# SH1-MCU.net
KiCad netlist of a schematic drawn in Altium Designer
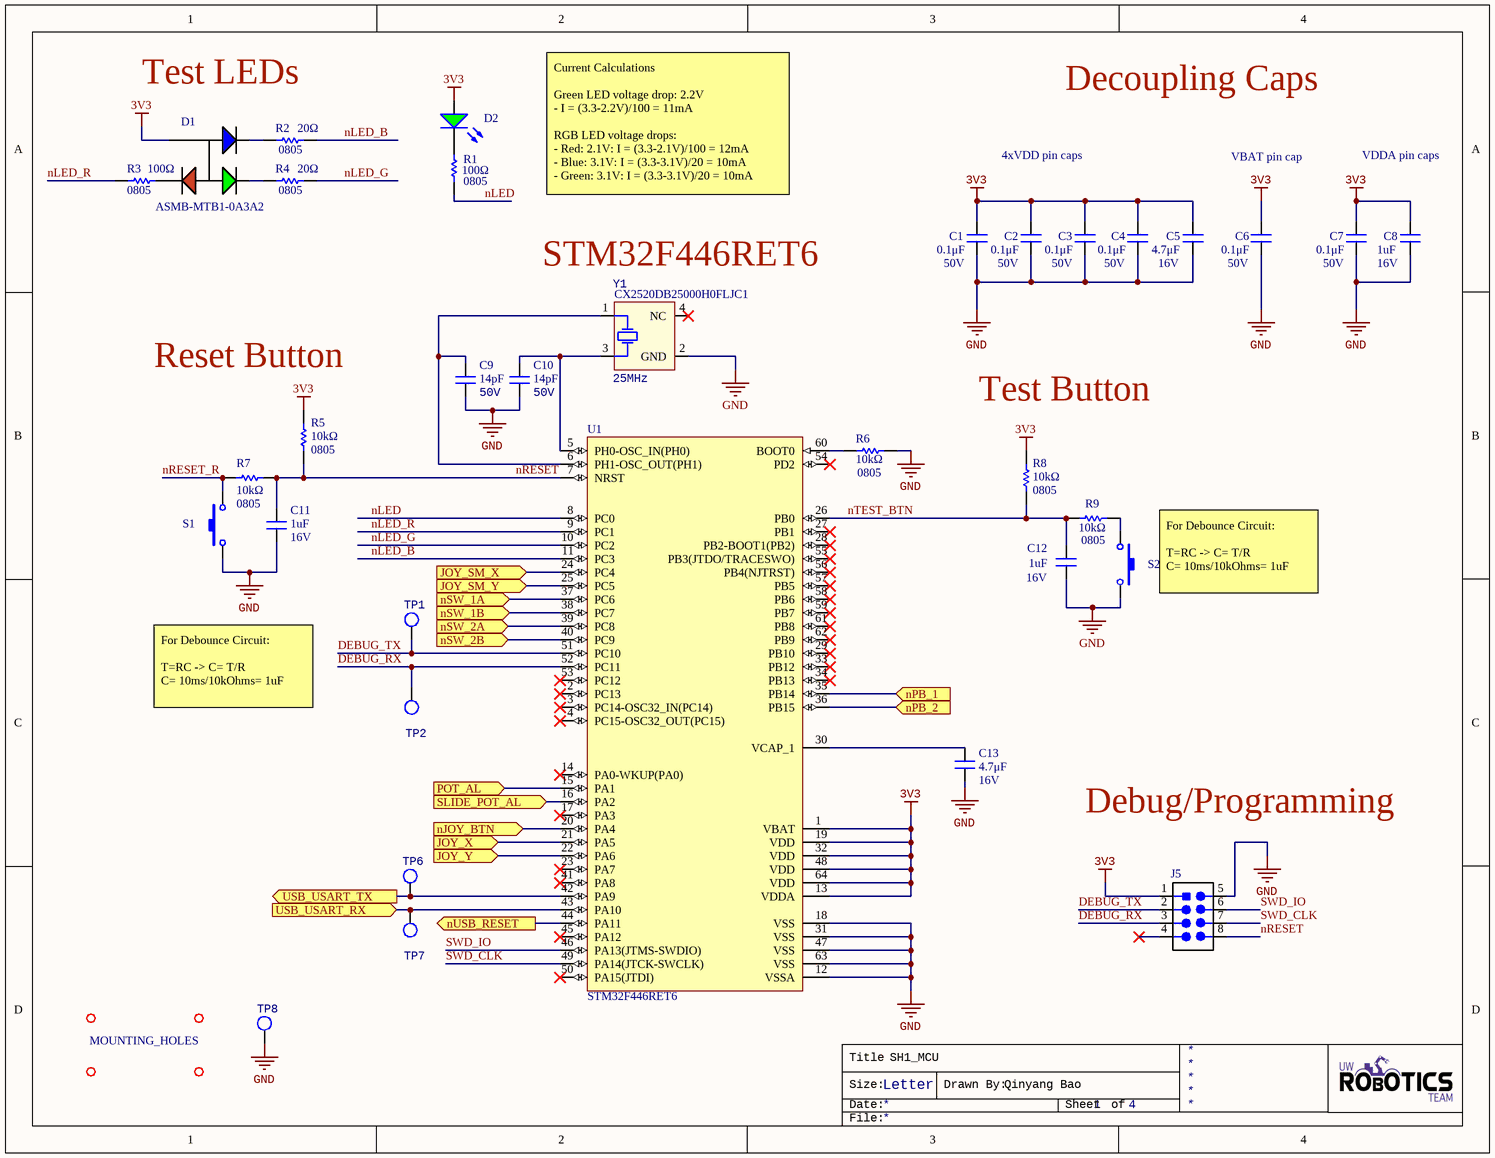
[diagram p0: SH1-MCU.SchDoc]

(export (version "E")
  (design (tool "Eeschema 10.0.6"))
  (components
    (comp (ref "C1")
      (value "0.1μF")
      (footprint "CAPC2012X140N")
      (description "CAP CER 0.1UF 50V X7R 0805")
      (fields (field (name "TOLERANCE") "10%") (field (name "VOLTAGE RATING") "50V"))
      (libsource (lib "UWRT_Schematic_Library_2020") (part "CAP_0.1uF_50V_0805"))
    )
    (comp (ref "C2")
      (value "0.1μF")
      (footprint "CAPC2012X140N")
      (description "CAP CER 0.1UF 50V X7R 0805")
      (fields (field (name "TOLERANCE") "10%") (field (name "VOLTAGE RATING") "50V"))
      (libsource (lib "UWRT_Schematic_Library_2020") (part "CAP_0.1uF_50V_0805"))
    )
    (comp (ref "C3")
      (value "0.1μF")
      (footprint "CAPC2012X140N")
      (description "CAP CER 0.1UF 50V X7R 0805")
      (fields (field (name "TOLERANCE") "10%") (field (name "VOLTAGE RATING") "50V"))
      (libsource (lib "UWRT_Schematic_Library_2020") (part "CAP_0.1uF_50V_0805"))
    )
    (comp (ref "C4")
      (value "0.1μF")
      (footprint "CAPC2012X140N")
      (description "CAP CER 0.1UF 50V X7R 0805")
      (fields (field (name "TOLERANCE") "10%") (field (name "VOLTAGE RATING") "50V"))
      (libsource (lib "UWRT_Schematic_Library_2020") (part "CAP_0.1uF_50V_0805"))
    )
    (comp (ref "C5")
      (value "4.7μF")
      (footprint "CAPC2012X140N")
      (description "CAP CER 4.7UF 16V X5R 0805")
      (fields
        (field (name "TOLERANCE") "10%")
        (field (name "VOLTAGE RATING") "16V")
        (field (name "Comment") "CAP_4.7uF_16V_0805")
      )
      (libsource (lib "UWRT_Schematic_Library_2020") (part "CAP_4.7uF_16V_0805"))
    )
    (comp (ref "C6")
      (value "0.1μF")
      (footprint "CAPC2012X140N")
      (description "CAP CER 0.1UF 50V X7R 0805")
      (fields (field (name "TOLERANCE") "10%") (field (name "VOLTAGE RATING") "50V"))
      (libsource (lib "UWRT_Schematic_Library_2020") (part "CAP_0.1uF_50V_0805"))
    )
    (comp (ref "C7")
      (value "0.1μF")
      (footprint "CAPC2012X140N")
      (description "CAP CER 0.1UF 50V X7R 0805")
      (fields (field (name "TOLERANCE") "10%") (field (name "VOLTAGE RATING") "50V"))
      (libsource (lib "UWRT_Schematic_Library_2020") (part "CAP_0.1uF_50V_0805"))
    )
    (comp (ref "C8")
      (value "1uF")
      (footprint "CAPC2012X140N")
      (description "CAP CER 1UF 16V X7R 0805")
      (fields
        (field (name "TOLERANCE") "10%")
        (field (name "VOLTAGE RATING") "16V")
        (field (name "Comment") "CAP_1uF_16V_0805")
      )
      (libsource (lib "UWRT_Schematic_Library_2020") (part "CAP_1uF_16V_0805"))
    )
    (comp (ref "C9")
      (value "14pF")
      (footprint "CAPC0603(1608)55_N")
      (description "Cap Ceramic 14pF 50V C0G 5% SMD 0603 125C Cardboard T/R")
      (fields
        (field (name "TOLERANCE") "5%")
        (field (name "VOLTAGE RATING (DC)") "50V")
        (field (name "Comment") "CL10C140JB8NNNC")
      )
      (libsource (lib "UWRT_Schematic_Library_2020") (part "CL10C140JB8NNNC"))
    )
    (comp (ref "C10")
      (value "14pF")
      (footprint "CAPC0603(1608)55_N")
      (description "Cap Ceramic 14pF 50V C0G 5% SMD 0603 125C Cardboard T/R")
      (fields
        (field (name "TOLERANCE") "5%")
        (field (name "VOLTAGE RATING (DC)") "50V")
        (field (name "Comment") "CL10C140JB8NNNC")
      )
      (libsource (lib "UWRT_Schematic_Library_2020") (part "CL10C140JB8NNNC"))
    )
    (comp (ref "C11")
      (value "1uF")
      (footprint "CAPC2012X140N")
      (description "CAP CER 1UF 16V X7R 0805")
      (fields
        (field (name "TOLERANCE") "10%")
        (field (name "VOLTAGE RATING") "16V")
        (field (name "Comment") "CAP_1uF_16V_0805")
      )
      (libsource (lib "UWRT_Schematic_Library_2020") (part "CAP_1uF_16V_0805"))
    )
    (comp (ref "C12")
      (value "1uF")
      (footprint "CAPC2012X140N")
      (description "CAP CER 1UF 16V X7R 0805")
      (fields
        (field (name "TOLERANCE") "10%")
        (field (name "VOLTAGE RATING") "16V")
        (field (name "Comment") "CAP_1uF_16V_0805")
      )
      (libsource (lib "UWRT_Schematic_Library_2020") (part "CAP_1uF_16V_0805"))
    )
    (comp (ref "C13")
      (value "4.7μF")
      (footprint "CAPC2012X140N")
      (description "CAP CER 4.7UF 16V X5R 0805")
      (fields
        (field (name "TOLERANCE") "10%")
        (field (name "VOLTAGE RATING") "16V")
        (field (name "Comment") "CAP_4.7uF_16V_0805")
      )
      (libsource (lib "UWRT_Schematic_Library_2020") (part "CAP_4.7uF_16V_0805"))
    )
    (comp (ref "D1")
      (value "LED_RGB")
      (footprint "LED_RGB")
      (description "LED RGB DIFFUSED 4PLCC SMD")
      (fields (field (name "MANUFACTURER PART NUMBER 1") "ASMB-MTB1-0A3A2"))
      (libsource (lib "UWRT_Schematic_Library_2020") (part "LED_RGB"))
    )
    (comp (ref "D2")
      (value "LG R971-KN-1")
      (footprint "LED_0805_LINE")
      (description "LED GREEN DIFFUSED 0805 SMD")
      (libsource (lib "UWRT_Schematic_Library_2020") (part "DIO_LED_G"))
    )
    (comp (ref "J5")
      (value "HEADER 4X2")
      (footprint "HEADER_2X4")
      (description "CONN HEADER VERT 8POS 2.54MM")
      (libsource (lib "UWRT_Schematic_Library_2020") (part "HEADER 4X2"))
    )
    (comp (ref "MH1")
      (value "MOUNTING_HOLES")
      (footprint "MOUNTING_HOLE")
      (description "6cm x 6cm")
      (libsource (lib "UWRT_Schematic_Library_2020") (part "MOUNTING_HOLES"))
    )
    (comp (ref "MH2")
      (value "MOUNTING_HOLES")
      (footprint "MOUNTING_HOLE")
      (description "6cm x 6cm")
      (libsource (lib "UWRT_Schematic_Library_2020") (part "MOUNTING_HOLES"))
    )
    (comp (ref "MH3")
      (value "MOUNTING_HOLES")
      (footprint "MOUNTING_HOLE")
      (description "6cm x 6cm")
      (libsource (lib "UWRT_Schematic_Library_2020") (part "MOUNTING_HOLES"))
    )
    (comp (ref "MH4")
      (value "MOUNTING_HOLES")
      (footprint "MOUNTING_HOLE")
      (description "6cm x 6cm")
      (libsource (lib "UWRT_Schematic_Library_2020") (part "MOUNTING_HOLES"))
    )
    (comp (ref "R1")
      (value "100Ω")
      (footprint "RESC2012X60N")
      (description "RES SMD 100 OHM 1% 1/8W 0805")
      (fields (field (name "CASE CODE (IMPERIAL)") "0805") (field (name "Comment") "RES_100Ω_0805"))
      (libsource (lib "UWRT_Schematic_Library_2020") (part "RES_100Ω_0805"))
    )
    (comp (ref "R2")
      (value "20Ω")
      (footprint "RESC2012X60N")
      (description "RES SMD 20 OHM 1% 1/8W 0805")
      (fields
        (field (name "CASE CODE (IMPERIAL)") "0805")
        (field (name "TOLERANCE") "1%")
        (field (name "Comment") "RES_20Ω_0805")
      )
      (libsource (lib "UWRT_Schematic_Library_2020") (part "RES_20Ω_0805"))
    )
    (comp (ref "R3")
      (value "100Ω")
      (footprint "RESC2012X60N")
      (description "RES SMD 100 OHM 1% 1/8W 0805")
      (fields (field (name "CASE CODE (IMPERIAL)") "0805") (field (name "Comment") "RES_100Ω_0805"))
      (libsource (lib "UWRT_Schematic_Library_2020") (part "RES_100Ω_0805"))
    )
    (comp (ref "R4")
      (value "20Ω")
      (footprint "RESC2012X60N")
      (description "RES SMD 20 OHM 1% 1/8W 0805")
      (fields
        (field (name "CASE CODE (IMPERIAL)") "0805")
        (field (name "TOLERANCE") "1%")
        (field (name "Comment") "RES_20Ω_0805")
      )
      (libsource (lib "UWRT_Schematic_Library_2020") (part "RES_20Ω_0805"))
    )
    (comp (ref "R5")
      (value "10kΩ")
      (footprint "RESC2012X60N")
      (description "RES SMD 10K OHM 1% 1/8W 0805")
      (fields
        (field (name "CASE CODE (IMPERIAL)") "0805")
        (field (name "TOLERANCE") "1%")
        (field (name "Comment") "RES_10kΩ_0805")
      )
      (libsource (lib "UWRT_Schematic_Library_2020") (part "RES_10kΩ_0805"))
    )
    (comp (ref "R6")
      (value "10kΩ")
      (footprint "RESC2012X60N")
      (description "RES SMD 10K OHM 1% 1/8W 0805")
      (fields
        (field (name "CASE CODE (IMPERIAL)") "0805")
        (field (name "TOLERANCE") "1%")
        (field (name "Comment") "RES_10kΩ_0805")
      )
      (libsource (lib "UWRT_Schematic_Library_2020") (part "RES_10kΩ_0805"))
    )
    (comp (ref "R7")
      (value "10kΩ")
      (footprint "RESC2012X60N")
      (description "RES SMD 10K OHM 1% 1/8W 0805")
      (fields
        (field (name "CASE CODE (IMPERIAL)") "0805")
        (field (name "TOLERANCE") "1%")
        (field (name "Comment") "RES_10kΩ_0805")
      )
      (libsource (lib "UWRT_Schematic_Library_2020") (part "RES_10kΩ_0805"))
    )
    (comp (ref "R8")
      (value "10kΩ")
      (footprint "RESC2012X60N")
      (description "RES SMD 10K OHM 1% 1/8W 0805")
      (fields
        (field (name "CASE CODE (IMPERIAL)") "0805")
        (field (name "TOLERANCE") "1%")
        (field (name "Comment") "RES_10kΩ_0805")
      )
      (libsource (lib "UWRT_Schematic_Library_2020") (part "RES_10kΩ_0805"))
    )
    (comp (ref "R9")
      (value "10kΩ")
      (footprint "RESC2012X60N")
      (description "RES SMD 10K OHM 1% 1/8W 0805")
      (fields
        (field (name "CASE CODE (IMPERIAL)") "0805")
        (field (name "TOLERANCE") "1%")
        (field (name "Comment") "RES_10kΩ_0805")
      )
      (libsource (lib "UWRT_Schematic_Library_2020") (part "RES_10kΩ_0805"))
    )
    (comp (ref "S1")
      (value "SW_TACTILE")
      (footprint "B3U-1000P")
      (description "Tactile Switch (Grey)")
      (libsource (lib "UWRT_Schematic_Library_2020") (part "SW_TACTILE"))
    )
    (comp (ref "S2")
      (value "SW_TACTILE")
      (footprint "B3U-1000P")
      (description "Tactile Switch (Grey)")
      (libsource (lib "UWRT_Schematic_Library_2020") (part "SW_TACTILE"))
    )
    (comp (ref "TP1")
      (value "TESTPOINT_LOOP")
      (footprint "TESTPOINT_LOOP")
      (description "Loop testpoint through-hole pad")
      (libsource (lib "UWRT_Schematic_Library_2020") (part "TESTPOINT_LOOP"))
    )
    (comp (ref "TP2")
      (value "TESTPOINT_LOOP")
      (footprint "TESTPOINT_LOOP")
      (description "Loop testpoint through-hole pad")
      (libsource (lib "UWRT_Schematic_Library_2020") (part "TESTPOINT_LOOP"))
    )
    (comp (ref "TP6")
      (value "TESTPOINT_LOOP")
      (footprint "TESTPOINT_LOOP")
      (description "Loop testpoint through-hole pad")
      (libsource (lib "UWRT_Schematic_Library_2020") (part "TESTPOINT_LOOP"))
    )
    (comp (ref "TP7")
      (value "TESTPOINT_LOOP")
      (footprint "TESTPOINT_LOOP")
      (description "Loop testpoint through-hole pad")
      (libsource (lib "UWRT_Schematic_Library_2020") (part "TESTPOINT_LOOP"))
    )
    (comp (ref "TP8")
      (value "TESTPOINT_LOOP")
      (footprint "TESTPOINT_LOOP")
      (description "Loop testpoint through-hole pad")
      (libsource (lib "UWRT_Schematic_Library_2020") (part "TESTPOINT_LOOP"))
    )
    (comp (ref "U1")
      (value "STM32F446RET6")
      (footprint "STM-LQFP64_L")
      (libsource (lib "UWRT_Schematic_Library_2020") (part "MCU_STM32F446RET6"))
    )
    (comp (ref "Y1")
      (value "CRYSTAL_25MHZ")
      (footprint "SOIC254P1016X440-4N")
      (description "CRYSTAL 25.0000MHZ 12PF SMD")
      (fields
        (field (name "MANUFACTURER PART NUMBER 1") "CX2520DB25000H0FLJC1")
        (field (name "FREQUENCY") "25MHz")
      )
      (libsource (lib "UWRT_Schematic_Library_2020") (part "CRYSTAL_25MHZ"))
    )
  )
  (nets
    (net (code "1") (name "/DEBUG_RX") (class "Default")
      (node (ref "J5") (pin "3") (pinfunction "3_3") (pintype "passive"))
      (node (ref "TP2") (pin "1") (pintype "passive"))
      (node (ref "U1") (pin "52") (pinfunction "PC11_52") (pintype "bidirectional"))
    )
    (net (code "2") (name "/DEBUG_TX") (class "Default")
      (node (ref "J5") (pin "2") (pinfunction "2_2") (pintype "passive"))
      (node (ref "TP1") (pin "1") (pintype "passive"))
      (node (ref "U1") (pin "51") (pinfunction "PC10_51") (pintype "bidirectional"))
    )
    (net (code "3") (name "/JOY_SM_X") (class "Default")
      (node (ref "U1") (pin "24") (pinfunction "PC4_24") (pintype "bidirectional"))
    )
    (net (code "4") (name "/JOY_SM_Y") (class "Default")
      (node (ref "U1") (pin "25") (pinfunction "PC5_25") (pintype "bidirectional"))
    )
    (net (code "5") (name "/JOY_X") (class "Default")
      (node (ref "U1") (pin "21") (pinfunction "PA5_21") (pintype "bidirectional"))
    )
    (net (code "6") (name "/JOY_Y") (class "Default")
      (node (ref "U1") (pin "22") (pinfunction "PA6_22") (pintype "bidirectional"))
    )
    (net (code "7") (name "/POT_AL") (class "Default")
      (node (ref "U1") (pin "15") (pinfunction "PA1_15") (pintype "bidirectional"))
    )
    (net (code "8") (name "/SLIDE_POT_AL") (class "Default")
      (node (ref "U1") (pin "16") (pinfunction "PA2_16") (pintype "bidirectional"))
    )
    (net (code "9") (name "/SWD_CLK") (class "Default")
      (node (ref "J5") (pin "7") (pinfunction "3_7") (pintype "passive"))
      (node (ref "U1") (pin "49") (pinfunction "PA14(JTCK-SWCLK)_49") (pintype "bidirectional"))
    )
    (net (code "10") (name "/SWD_IO") (class "Default")
      (node (ref "J5") (pin "6") (pinfunction "2_6") (pintype "passive"))
      (node (ref "U1") (pin "46") (pinfunction "PA13(JTMS-SWDIO)_46") (pintype "bidirectional"))
    )
    (net (code "11") (name "/USB_USART_RX") (class "Default")
      (node (ref "TP7") (pin "1") (pintype "passive"))
      (node (ref "U1") (pin "43") (pinfunction "PA10_43") (pintype "bidirectional"))
    )
    (net (code "12") (name "/USB_USART_TX") (class "Default")
      (node (ref "TP6") (pin "1") (pintype "passive"))
      (node (ref "U1") (pin "42") (pinfunction "PA9_42") (pintype "bidirectional"))
    )
    (net (code "13") (name "/nJOY_BTN") (class "Default")
      (node (ref "U1") (pin "20") (pinfunction "PA4_20") (pintype "bidirectional"))
    )
    (net (code "14") (name "/nLED") (class "Default")
      (node (ref "R1") (pin "1") (pinfunction "1_1") (pintype "passive"))
      (node (ref "U1") (pin "8") (pinfunction "PC0_8") (pintype "bidirectional"))
    )
    (net (code "15") (name "/nLED_B") (class "Default")
      (node (ref "R2") (pin "2") (pinfunction "2_2") (pintype "passive"))
      (node (ref "U1") (pin "11") (pinfunction "PC3_11") (pintype "bidirectional"))
    )
    (net (code "16") (name "/nLED_G") (class "Default")
      (node (ref "R4") (pin "2") (pinfunction "2_2") (pintype "passive"))
      (node (ref "U1") (pin "10") (pinfunction "PC2_10") (pintype "bidirectional"))
    )
    (net (code "17") (name "/nLED_R") (class "Default")
      (node (ref "R3") (pin "1") (pinfunction "1_1") (pintype "passive"))
      (node (ref "U1") (pin "9") (pinfunction "PC1_9") (pintype "bidirectional"))
    )
    (net (code "18") (name "/nPB_1") (class "Default")
      (node (ref "U1") (pin "35") (pinfunction "PB14_35") (pintype "bidirectional"))
    )
    (net (code "19") (name "/nPB_2") (class "Default")
      (node (ref "U1") (pin "36") (pinfunction "PB15_36") (pintype "bidirectional"))
    )
    (net (code "20") (name "/nRESET") (class "Default")
      (node (ref "C11") (pin "2") (pinfunction "2_2") (pintype "passive"))
      (node (ref "J5") (pin "8") (pinfunction "4_8") (pintype "passive"))
      (node (ref "R5") (pin "1") (pinfunction "1_1") (pintype "passive"))
      (node (ref "R7") (pin "2") (pinfunction "2_2") (pintype "passive"))
      (node (ref "U1") (pin "7") (pinfunction "NRST_7") (pintype "bidirectional"))
    )
    (net (code "21") (name "/nRESET_R") (class "Default")
      (node (ref "R7") (pin "1") (pinfunction "1_1") (pintype "passive"))
      (node (ref "S1") (pin "1") (pinfunction "1_1") (pintype "passive"))
    )
    (net (code "22") (name "/nSW_1A") (class "Default")
      (node (ref "U1") (pin "37") (pinfunction "PC6_37") (pintype "bidirectional"))
    )
    (net (code "23") (name "/nSW_1B") (class "Default")
      (node (ref "U1") (pin "38") (pinfunction "PC7_38") (pintype "bidirectional"))
    )
    (net (code "24") (name "/nSW_2A") (class "Default")
      (node (ref "U1") (pin "39") (pinfunction "PC8_39") (pintype "bidirectional"))
    )
    (net (code "25") (name "/nSW_2B") (class "Default")
      (node (ref "U1") (pin "40") (pinfunction "PC9_40") (pintype "bidirectional"))
    )
    (net (code "26") (name "/nTEST_BTN") (class "Default")
      (node (ref "C12") (pin "2") (pinfunction "2_2") (pintype "passive"))
      (node (ref "R8") (pin "1") (pinfunction "1_1") (pintype "passive"))
      (node (ref "R9") (pin "1") (pinfunction "1_1") (pintype "passive"))
      (node (ref "U1") (pin "26") (pinfunction "PB0_26") (pintype "bidirectional"))
    )
    (net (code "27") (name "/nUSB_RESET") (class "Default")
      (node (ref "U1") (pin "44") (pinfunction "PA11_44") (pintype "bidirectional"))
    )
    (net (code "28") (name "3V3") (class "Default")
      (node (ref "C1") (pin "2") (pinfunction "2_2") (pintype "passive"))
      (node (ref "C2") (pin "2") (pinfunction "2_2") (pintype "passive"))
      (node (ref "C3") (pin "2") (pinfunction "2_2") (pintype "passive"))
      (node (ref "C4") (pin "2") (pinfunction "2_2") (pintype "passive"))
      (node (ref "C5") (pin "2") (pinfunction "2_2") (pintype "passive"))
      (node (ref "C6") (pin "2") (pinfunction "2_2") (pintype "passive"))
      (node (ref "C7") (pin "2") (pinfunction "2_2") (pintype "passive"))
      (node (ref "C8") (pin "2") (pinfunction "2_2") (pintype "passive"))
      (node (ref "D1") (pin "4") (pinfunction "9_4") (pintype "passive"))
      (node (ref "D2") (pin "1") (pinfunction "A_1") (pintype "passive"))
      (node (ref "J5") (pin "1") (pinfunction "VCC_1") (pintype "passive"))
      (node (ref "R5") (pin "2") (pinfunction "2_2") (pintype "passive"))
      (node (ref "R8") (pin "2") (pinfunction "2_2") (pintype "passive"))
      (node (ref "U1") (pin "1") (pinfunction "VBAT_1") (pintype "power_in"))
      (node (ref "U1") (pin "13") (pinfunction "VDDA_13") (pintype "power_in"))
      (node (ref "U1") (pin "19") (pinfunction "VDD_19") (pintype "power_in"))
      (node (ref "U1") (pin "32") (pinfunction "VDD_32") (pintype "power_in"))
      (node (ref "U1") (pin "48") (pinfunction "VDD_48") (pintype "power_in"))
      (node (ref "U1") (pin "64") (pinfunction "VDD_64") (pintype "power_in"))
    )
    (net (code "29") (name "GND") (class "Default")
      (node (ref "C1") (pin "1") (pinfunction "1_1") (pintype "passive"))
      (node (ref "C10") (pin "1") (pinfunction "1_1") (pintype "passive"))
      (node (ref "C11") (pin "1") (pinfunction "1_1") (pintype "passive"))
      (node (ref "C12") (pin "1") (pinfunction "1_1") (pintype "passive"))
      (node (ref "C13") (pin "1") (pinfunction "1_1") (pintype "passive"))
      (node (ref "C2") (pin "1") (pinfunction "1_1") (pintype "passive"))
      (node (ref "C3") (pin "1") (pinfunction "1_1") (pintype "passive"))
      (node (ref "C4") (pin "1") (pinfunction "1_1") (pintype "passive"))
      (node (ref "C5") (pin "1") (pinfunction "1_1") (pintype "passive"))
      (node (ref "C6") (pin "1") (pinfunction "1_1") (pintype "passive"))
      (node (ref "C7") (pin "1") (pinfunction "1_1") (pintype "passive"))
      (node (ref "C8") (pin "1") (pinfunction "1_1") (pintype "passive"))
      (node (ref "C9") (pin "1") (pinfunction "1_1") (pintype "passive"))
      (node (ref "J5") (pin "5") (pinfunction "GND_5") (pintype "passive"))
      (node (ref "R6") (pin "2") (pinfunction "2_2") (pintype "passive"))
      (node (ref "S1") (pin "2") (pinfunction "2_2") (pintype "passive"))
      (node (ref "S2") (pin "2") (pinfunction "2_2") (pintype "passive"))
      (node (ref "TP8") (pin "1") (pintype "passive"))
      (node (ref "U1") (pin "12") (pinfunction "VSSA_12") (pintype "power_in"))
      (node (ref "U1") (pin "18") (pinfunction "VSS_18") (pintype "power_in"))
      (node (ref "U1") (pin "31") (pinfunction "VSS_31") (pintype "power_in"))
      (node (ref "U1") (pin "47") (pinfunction "VSS_47") (pintype "power_in"))
      (node (ref "U1") (pin "63") (pinfunction "VSS_63") (pintype "power_in"))
      (node (ref "Y1") (pin "2") (pinfunction "GND_2") (pintype "power_in"))
    )
    (net (code "30") (name "Net-(D1-10)") (class "Default")
      (node (ref "D1") (pin "3") (pinfunction "10_3") (pintype "passive"))
      (node (ref "R2") (pin "1") (pinfunction "1_1") (pintype "passive"))
    )
    (net (code "31") (name "Net-(D1-11)") (class "Default")
      (node (ref "D1") (pin "1") (pinfunction "11_1") (pintype "passive"))
      (node (ref "R3") (pin "2") (pinfunction "2_2") (pintype "passive"))
    )
    (net (code "32") (name "Net-(D1-12)") (class "Default")
      (node (ref "D1") (pin "2") (pinfunction "12_2") (pintype "passive"))
      (node (ref "R4") (pin "1") (pinfunction "1_1") (pintype "passive"))
    )
    (net (code "33") (name "Net-(D2-K)") (class "Default")
      (node (ref "D2") (pin "2") (pinfunction "K_2") (pintype "passive"))
      (node (ref "R1") (pin "2") (pinfunction "2_2") (pintype "passive"))
    )
    (net (code "34") (name "Net-(R9-Pad2)") (class "Default")
      (node (ref "R9") (pin "2") (pinfunction "2_2") (pintype "passive"))
      (node (ref "S2") (pin "1") (pinfunction "1_1") (pintype "passive"))
    )
    (net (code "35") (name "Net-(U1-BOOT0)") (class "Default")
      (node (ref "R6") (pin "1") (pinfunction "1_1") (pintype "passive"))
      (node (ref "U1") (pin "60") (pinfunction "BOOT0_60") (pintype "input"))
    )
    (net (code "36") (name "Net-(U1-PH0-OSC_IN(PH0))") (class "Default")
      (node (ref "C10") (pin "2") (pinfunction "2_2") (pintype "passive"))
      (node (ref "U1") (pin "5") (pinfunction "PH0-OSC_IN(PH0)_5") (pintype "bidirectional"))
      (node (ref "Y1") (pin "3") (pinfunction "HOT_3") (pintype "passive"))
    )
    (net (code "37") (name "Net-(U1-PH1-OSC_OUT(PH1))") (class "Default")
      (node (ref "C9") (pin "2") (pinfunction "2_2") (pintype "passive"))
      (node (ref "U1") (pin "6") (pinfunction "PH1-OSC_OUT(PH1)_6") (pintype "bidirectional"))
      (node (ref "Y1") (pin "1") (pinfunction "HOT_1") (pintype "passive"))
    )
    (net (code "38") (name "Net-(U1-VCAP_1)") (class "Default")
      (node (ref "C13") (pin "2") (pinfunction "2_2") (pintype "passive"))
      (node (ref "U1") (pin "30") (pinfunction "VCAP_1_30") (pintype "passive"))
    )
    (net (code "39") (name "unconnected-(J5-Pad4)") (class "Default")
      (node (ref "J5") (pin "4") (pinfunction "4_4") (pintype "passive+no_connect"))
    )
    (net (code "40") (name "unconnected-(U1-PA0-WKUP(PA0)-Pad14)") (class "Default")
      (node (ref "U1") (pin "14") (pinfunction "PA0-WKUP(PA0)_14") (pintype "bidirectional+no_connect"))
    )
    (net (code "41") (name "unconnected-(U1-PA3-Pad17)") (class "Default")
      (node (ref "U1") (pin "17") (pinfunction "PA3_17") (pintype "bidirectional+no_connect"))
    )
    (net (code "42") (name "unconnected-(U1-PA7-Pad23)") (class "Default")
      (node (ref "U1") (pin "23") (pinfunction "PA7_23") (pintype "bidirectional+no_connect"))
    )
    (net (code "43") (name "unconnected-(U1-PA8-Pad41)") (class "Default")
      (node (ref "U1") (pin "41") (pinfunction "PA8_41") (pintype "bidirectional+no_connect"))
    )
    (net (code "44") (name "unconnected-(U1-PA12-Pad45)") (class "Default")
      (node (ref "U1") (pin "45") (pinfunction "PA12_45") (pintype "bidirectional+no_connect"))
    )
    (net (code "45") (name "unconnected-(U1-PA15(JTDI)-Pad50)") (class "Default")
      (node (ref "U1") (pin "50") (pinfunction "PA15(JTDI)_50") (pintype "bidirectional+no_connect"))
    )
    (net (code "46") (name "unconnected-(U1-PB1-Pad27)") (class "Default")
      (node (ref "U1") (pin "27") (pinfunction "PB1_27") (pintype "bidirectional+no_connect"))
    )
    (net (code "47") (name "unconnected-(U1-PB2-BOOT1(PB2)-Pad28)") (class "Default")
      (node (ref "U1") (pin "28") (pinfunction "PB2-BOOT1(PB2)_28") (pintype "bidirectional+no_connect"))
    )
    (net (code "48") (name "unconnected-(U1-PB3(JTDO{slash}TRACESWO)-Pad55)") (class "Default")
      (node (ref "U1") (pin "55") (pinfunction "PB3(JTDO/TRACESWO)_55") (pintype "bidirectional+no_connect"))
    )
    (net (code "49") (name "unconnected-(U1-PB4(NJTRST)-Pad56)") (class "Default")
      (node (ref "U1") (pin "56") (pinfunction "PB4(NJTRST)_56") (pintype "bidirectional+no_connect"))
    )
    (net (code "50") (name "unconnected-(U1-PB5-Pad57)") (class "Default")
      (node (ref "U1") (pin "57") (pinfunction "PB5_57") (pintype "bidirectional+no_connect"))
    )
    (net (code "51") (name "unconnected-(U1-PB6-Pad58)") (class "Default")
      (node (ref "U1") (pin "58") (pinfunction "PB6_58") (pintype "bidirectional+no_connect"))
    )
    (net (code "52") (name "unconnected-(U1-PB7-Pad59)") (class "Default")
      (node (ref "U1") (pin "59") (pinfunction "PB7_59") (pintype "bidirectional+no_connect"))
    )
    (net (code "53") (name "unconnected-(U1-PB8-Pad61)") (class "Default")
      (node (ref "U1") (pin "61") (pinfunction "PB8_61") (pintype "bidirectional+no_connect"))
    )
    (net (code "54") (name "unconnected-(U1-PB9-Pad62)") (class "Default")
      (node (ref "U1") (pin "62") (pinfunction "PB9_62") (pintype "bidirectional+no_connect"))
    )
    (net (code "55") (name "unconnected-(U1-PB10-Pad29)") (class "Default")
      (node (ref "U1") (pin "29") (pinfunction "PB10_29") (pintype "bidirectional+no_connect"))
    )
    (net (code "56") (name "unconnected-(U1-PB12-Pad33)") (class "Default")
      (node (ref "U1") (pin "33") (pinfunction "PB12_33") (pintype "bidirectional+no_connect"))
    )
    (net (code "57") (name "unconnected-(U1-PB13-Pad34)") (class "Default")
      (node (ref "U1") (pin "34") (pinfunction "PB13_34") (pintype "bidirectional+no_connect"))
    )
    (net (code "58") (name "unconnected-(U1-PC12-Pad53)") (class "Default")
      (node (ref "U1") (pin "53") (pinfunction "PC12_53") (pintype "bidirectional+no_connect"))
    )
    (net (code "59") (name "unconnected-(U1-PC13-Pad2)") (class "Default")
      (node (ref "U1") (pin "2") (pinfunction "PC13_2") (pintype "bidirectional+no_connect"))
    )
    (net (code "60") (name "unconnected-(U1-PC14-OSC32_IN(PC14)-Pad3)") (class "Default")
      (node (ref "U1") (pin "3") (pinfunction "PC14-OSC32_IN(PC14)_3") (pintype "bidirectional+no_connect"))
    )
    (net (code "61") (name "unconnected-(U1-PC15-OSC32_OUT(PC15)-Pad4)") (class "Default")
      (node (ref "U1") (pin "4") (pinfunction "PC15-OSC32_OUT(PC15)_4") (pintype "bidirectional+no_connect"))
    )
    (net (code "62") (name "unconnected-(U1-PD2-Pad54)") (class "Default")
      (node (ref "U1") (pin "54") (pinfunction "PD2_54") (pintype "bidirectional+no_connect"))
    )
    (net (code "63") (name "unconnected-(Y1-NC-Pad4)") (class "Default")
      (node (ref "Y1") (pin "4") (pinfunction "NC_4") (pintype "passive+no_connect"))
    )
  )
)
